# sheet3.net
KiCad netlist of a schematic drawn in Altium Designer
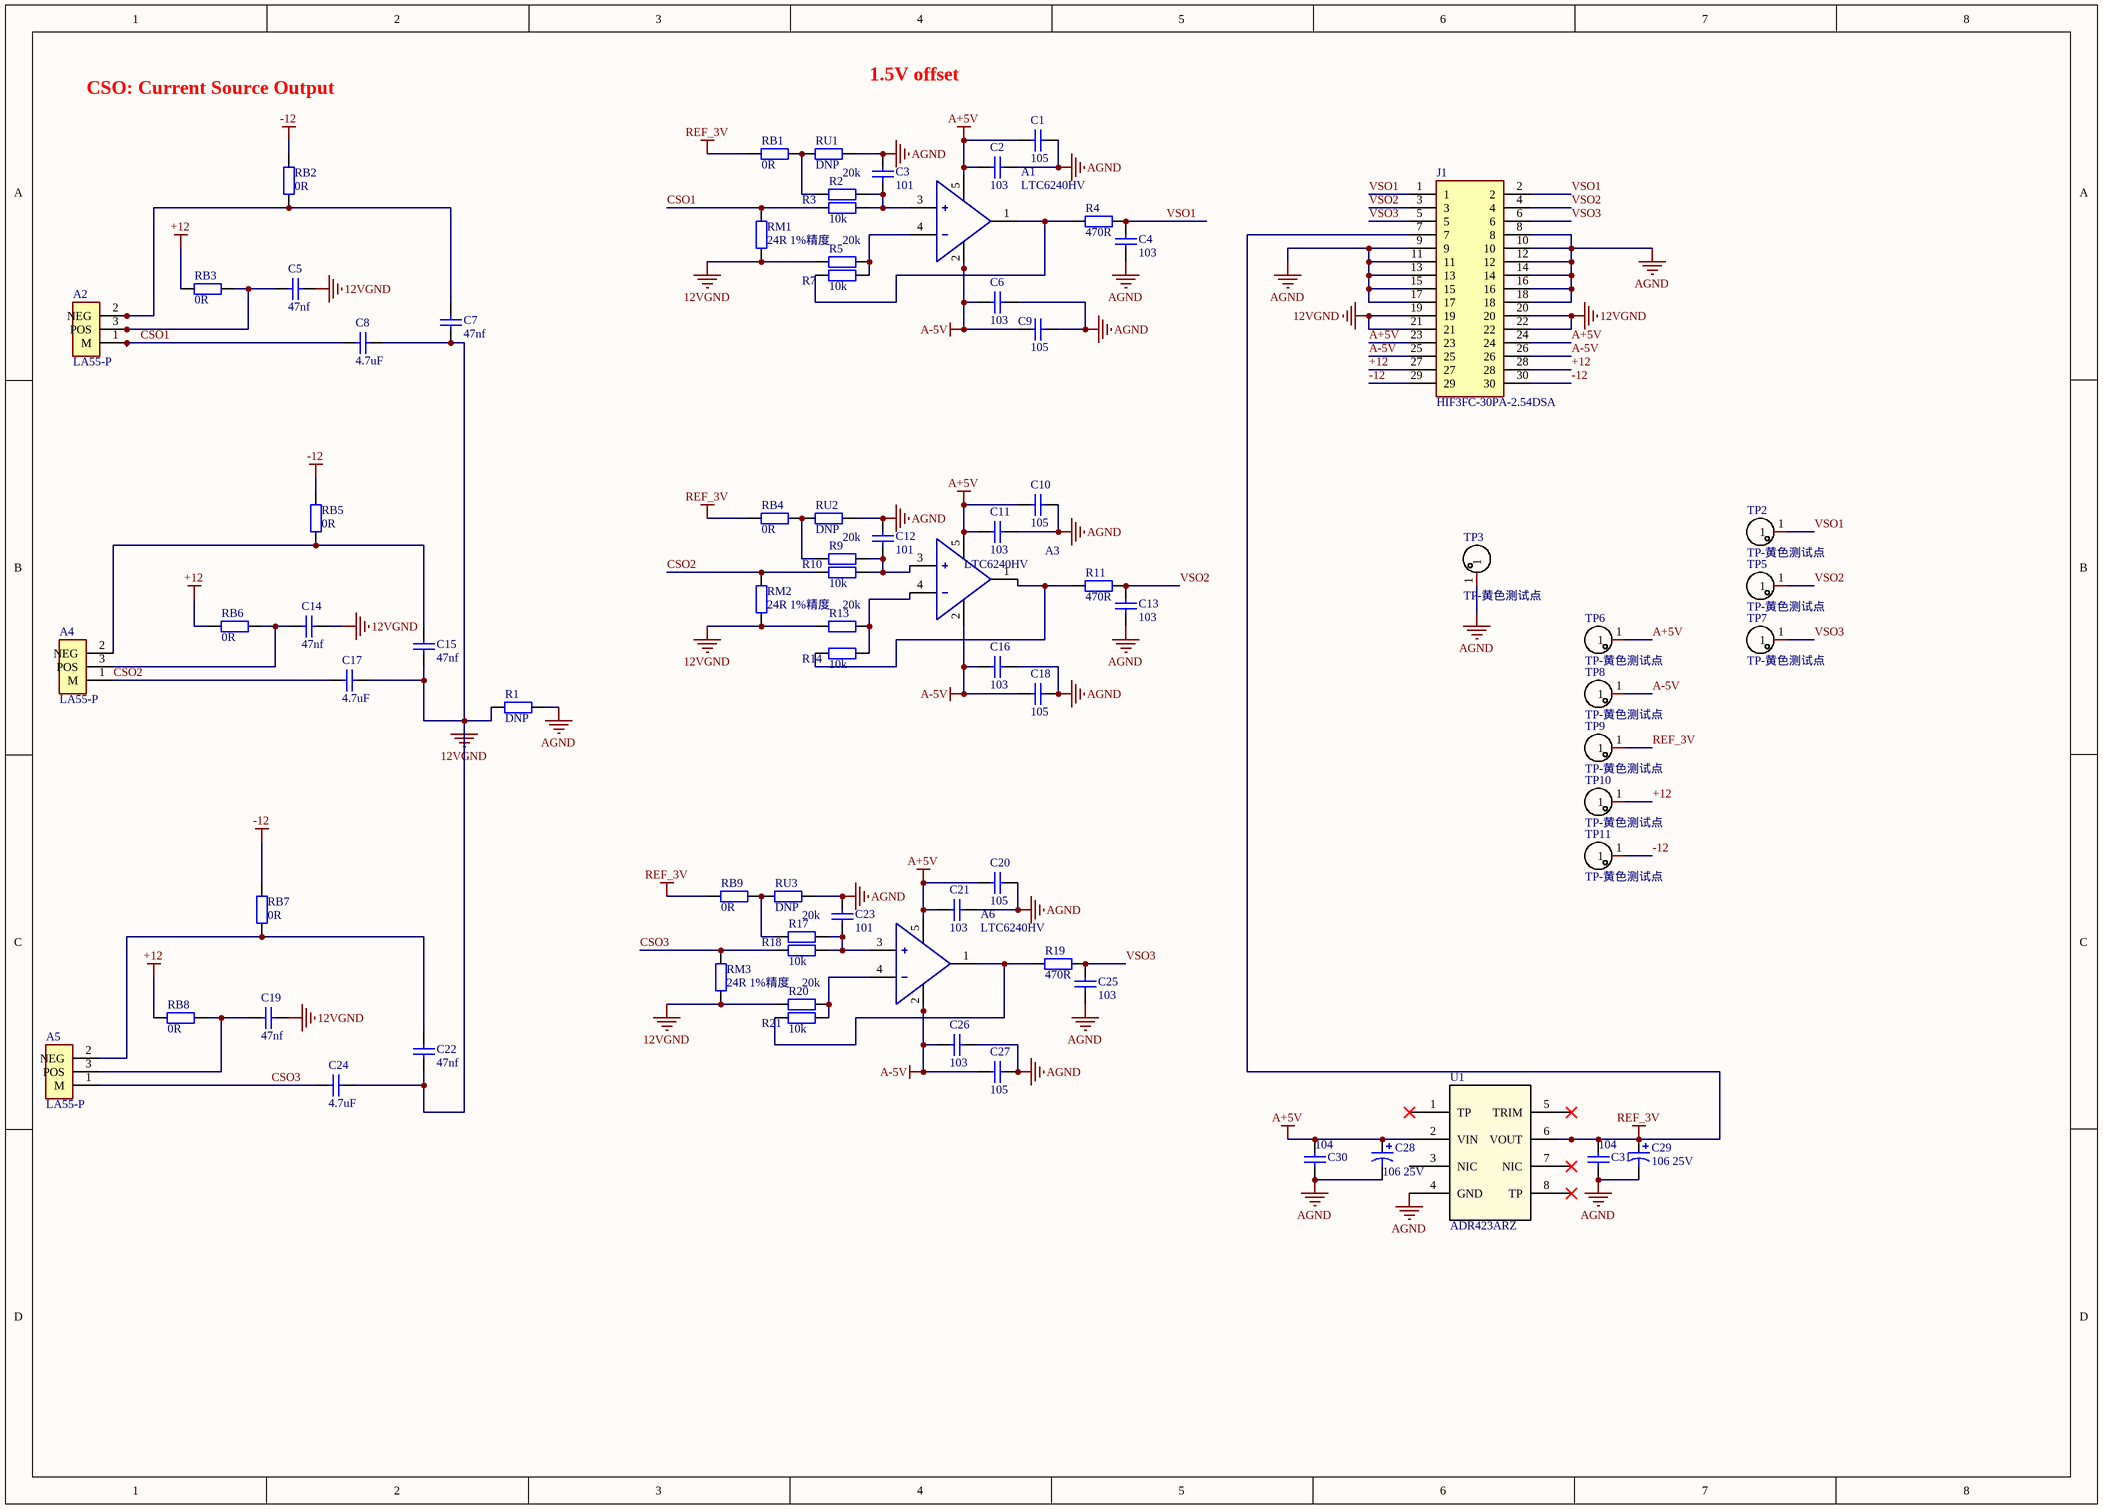
[diagram p0: sheet3.SchDoc]

(export (version "E")
  (design (tool "Eeschema 10.0.6"))
  (components
    (comp (ref "A1")
      (value "LTC6240HV")
      (footprint "SOT95P280X100-5N")
      (description "OP AMP, +-5.5V, 18MHZ, 10V/US, 5TSOT23")
      (libsource (lib "Project_Arsene") (part "AO_LTC6240HV"))
    )
    (comp (ref "A2")
      (value "LA55-P")
      (footprint "XDCR_LA55-P")
      (description "Current Sensor 50A 1 Channel Hall Effect, Closed Loop Bidirectional Module, Single Pass Through")
      (fields (field (name "MP") "LA 55-P") (field (name "MF") "LEM USA"))
      (libsource (lib "LA55-P") (part "LA55-P"))
    )
    (comp (ref "A3")
      (value "LTC6240HV")
      (footprint "SOT95P280X100-5N")
      (description "OP AMP, +-5.5V, 18MHZ, 10V/US, 5TSOT23")
      (libsource (lib "Project_Arsene") (part "AO_LTC6240HV"))
    )
    (comp (ref "A4")
      (value "LA55-P")
      (footprint "XDCR_LA55-P")
      (description "Current Sensor 50A 1 Channel Hall Effect, Closed Loop Bidirectional Module, Single Pass Through")
      (fields (field (name "MP") "LA 55-P") (field (name "MF") "LEM USA"))
      (libsource (lib "LA55-P") (part "LA55-P"))
    )
    (comp (ref "A5")
      (value "LA55-P")
      (footprint "XDCR_LA55-P")
      (description "Current Sensor 50A 1 Channel Hall Effect, Closed Loop Bidirectional Module, Single Pass Through")
      (fields (field (name "MP") "LA 55-P") (field (name "MF") "LEM USA"))
      (libsource (lib "LA55-P") (part "LA55-P"))
    )
    (comp (ref "A6")
      (value "LTC6240HV")
      (footprint "SOT95P280X100-5N")
      (description "OP AMP, +-5.5V, 18MHZ, 10V/US, 5TSOT23")
      (libsource (lib "Project_Arsene") (part "AO_LTC6240HV"))
    )
    (comp (ref "C1")
      (value "105")
      (footprint "0805")
      (description "Capacitor")
      (fields (field (name "PUBLISHER") "Altium Limited"))
      (libsource (lib "Miscellaneous Devices") (part "Cap"))
    )
    (comp (ref "C2")
      (value "103")
      (footprint "0805")
      (description "Capacitor")
      (fields (field (name "PUBLISHER") "Altium Limited"))
      (libsource (lib "Miscellaneous Devices") (part "Cap"))
    )
    (comp (ref "C3")
      (value "101")
      (footprint "0805")
      (description "Capacitor")
      (fields (field (name "PUBLISHER") "Altium Limited"))
      (libsource (lib "Miscellaneous Devices") (part "Cap"))
    )
    (comp (ref "C4")
      (value "103")
      (footprint "0805")
      (description "Capacitor")
      (fields (field (name "PUBLISHER") "Altium Limited"))
      (libsource (lib "Miscellaneous Devices") (part "Cap"))
    )
    (comp (ref "C5")
      (value "47nf")
      (footprint "0805")
      (description "Capacitor (Semiconductor SIM Model)")
      (fields (field (name "PUBLISHER") "Altium Limited"))
      (libsource (lib "Miscellaneous Devices") (part "Cap Semi"))
    )
    (comp (ref "C6")
      (value "103")
      (footprint "0805")
      (description "Capacitor")
      (fields (field (name "PUBLISHER") "Altium Limited"))
      (libsource (lib "Miscellaneous Devices") (part "Cap"))
    )
    (comp (ref "C7")
      (value "47nf")
      (footprint "0805")
      (description "Capacitor (Semiconductor SIM Model)")
      (fields (field (name "PUBLISHER") "Altium Limited"))
      (libsource (lib "Miscellaneous Devices") (part "Cap Semi"))
    )
    (comp (ref "C8")
      (value "4.7uF")
      (footprint "0805")
      (description "Capacitor (Semiconductor SIM Model)")
      (fields (field (name "PUBLISHER") "Altium Limited"))
      (libsource (lib "Miscellaneous Devices") (part "Cap Semi"))
    )
    (comp (ref "C9")
      (value "105")
      (footprint "0805")
      (description "Capacitor")
      (fields (field (name "PUBLISHER") "Altium Limited"))
      (libsource (lib "Miscellaneous Devices") (part "Cap"))
    )
    (comp (ref "C10")
      (value "105")
      (footprint "0805")
      (description "Capacitor")
      (fields (field (name "PUBLISHER") "Altium Limited"))
      (libsource (lib "Miscellaneous Devices") (part "Cap"))
    )
    (comp (ref "C11")
      (value "103")
      (footprint "0805")
      (description "Capacitor")
      (fields (field (name "PUBLISHER") "Altium Limited"))
      (libsource (lib "Miscellaneous Devices") (part "Cap"))
    )
    (comp (ref "C12")
      (value "101")
      (footprint "0805")
      (description "Capacitor")
      (fields (field (name "PUBLISHER") "Altium Limited"))
      (libsource (lib "Miscellaneous Devices") (part "Cap"))
    )
    (comp (ref "C13")
      (value "103")
      (footprint "0805")
      (description "Capacitor")
      (fields (field (name "PUBLISHER") "Altium Limited"))
      (libsource (lib "Miscellaneous Devices") (part "Cap"))
    )
    (comp (ref "C14")
      (value "47nf")
      (footprint "0805")
      (description "Capacitor (Semiconductor SIM Model)")
      (fields (field (name "PUBLISHER") "Altium Limited"))
      (libsource (lib "Miscellaneous Devices") (part "Cap Semi"))
    )
    (comp (ref "C15")
      (value "47nf")
      (footprint "0805")
      (description "Capacitor (Semiconductor SIM Model)")
      (fields (field (name "PUBLISHER") "Altium Limited"))
      (libsource (lib "Miscellaneous Devices") (part "Cap Semi"))
    )
    (comp (ref "C16")
      (value "103")
      (footprint "0805")
      (description "Capacitor")
      (fields (field (name "PUBLISHER") "Altium Limited"))
      (libsource (lib "Miscellaneous Devices") (part "Cap"))
    )
    (comp (ref "C17")
      (value "4.7uF")
      (footprint "0805")
      (description "Capacitor (Semiconductor SIM Model)")
      (fields (field (name "PUBLISHER") "Altium Limited"))
      (libsource (lib "Miscellaneous Devices") (part "Cap Semi"))
    )
    (comp (ref "C18")
      (value "105")
      (footprint "0805")
      (description "Capacitor")
      (fields (field (name "PUBLISHER") "Altium Limited"))
      (libsource (lib "Miscellaneous Devices") (part "Cap"))
    )
    (comp (ref "C19")
      (value "47nf")
      (footprint "0805")
      (description "Capacitor (Semiconductor SIM Model)")
      (fields (field (name "PUBLISHER") "Altium Limited"))
      (libsource (lib "Miscellaneous Devices") (part "Cap Semi"))
    )
    (comp (ref "C20")
      (value "105")
      (footprint "0805")
      (description "Capacitor")
      (fields (field (name "PUBLISHER") "Altium Limited"))
      (libsource (lib "Miscellaneous Devices") (part "Cap"))
    )
    (comp (ref "C21")
      (value "103")
      (footprint "0805")
      (description "Capacitor")
      (fields (field (name "PUBLISHER") "Altium Limited"))
      (libsource (lib "Miscellaneous Devices") (part "Cap"))
    )
    (comp (ref "C22")
      (value "47nf")
      (footprint "0805")
      (description "Capacitor (Semiconductor SIM Model)")
      (fields (field (name "PUBLISHER") "Altium Limited"))
      (libsource (lib "Miscellaneous Devices") (part "Cap Semi"))
    )
    (comp (ref "C23")
      (value "101")
      (footprint "0805")
      (description "Capacitor")
      (fields (field (name "PUBLISHER") "Altium Limited"))
      (libsource (lib "Miscellaneous Devices") (part "Cap"))
    )
    (comp (ref "C24")
      (value "4.7uF")
      (footprint "0805")
      (description "Capacitor (Semiconductor SIM Model)")
      (fields (field (name "PUBLISHER") "Altium Limited"))
      (libsource (lib "Miscellaneous Devices") (part "Cap Semi"))
    )
    (comp (ref "C25")
      (value "103")
      (footprint "0805")
      (description "Capacitor")
      (fields (field (name "PUBLISHER") "Altium Limited"))
      (libsource (lib "Miscellaneous Devices") (part "Cap"))
    )
    (comp (ref "C26")
      (value "103")
      (footprint "0805")
      (description "Capacitor")
      (fields (field (name "PUBLISHER") "Altium Limited"))
      (libsource (lib "Miscellaneous Devices") (part "Cap"))
    )
    (comp (ref "C27")
      (value "105")
      (footprint "0805")
      (description "Capacitor")
      (fields (field (name "PUBLISHER") "Altium Limited"))
      (libsource (lib "Miscellaneous Devices") (part "Cap"))
    )
    (comp (ref "C28")
      (value "106 25V")
      (footprint "1206 (钽电容)")
      (description "Polarized Capacitor (Surface Mount)")
      (fields (field (name "PUBLISHER") "Altium Limited"))
      (libsource (lib "Miscellaneous Devices") (part "Cap Pol3"))
    )
    (comp (ref "C29")
      (value "106 25V")
      (footprint "1206 (钽电容)")
      (description "Polarized Capacitor (Surface Mount)")
      (fields (field (name "PUBLISHER") "Altium Limited"))
      (libsource (lib "Miscellaneous Devices") (part "Cap Pol3"))
    )
    (comp (ref "C30")
      (value "104")
      (footprint "0805")
      (description "Capacitor (Semiconductor SIM Model)")
      (fields (field (name "PUBLISHER") "Altium Limited"))
      (libsource (lib "Miscellaneous Devices") (part "Cap Semi"))
    )
    (comp (ref "C31")
      (value "104")
      (footprint "0805")
      (description "Capacitor (Semiconductor SIM Model)")
      (fields (field (name "PUBLISHER") "Altium Limited"))
      (libsource (lib "Miscellaneous Devices") (part "Cap Semi"))
    )
    (comp (ref "J1")
      (value "HIF3FC-30PA-2.54DSA")
      (footprint "Project_Oshinoko:SHDR30W50P254_2X15_4560X850X1200P")
      (description "Connector")
      (fields
        (field (name "MANUFACTURER_PART_NUMBER") "HIF3FC-30PA-2.54DSA(71)")
        (field (name "MOUSER PART NUMBER") "798-HIF3FC30PA254D71")
      )
      (libsource (lib "Project_Arsene") (part "HIF3FC-30PA-2.54DSA"))
    )
    (comp (ref "R1")
      (value "DNP")
      (footprint "0805")
      (description "Resistor")
      (fields (field (name "PUBLISHER") "Altium Limited"))
      (libsource (lib "") (part "Res2_1"))
    )
    (comp (ref "R2")
      (value "20k")
      (footprint "0805")
      (description "Resistor")
      (fields (field (name "PUBLISHER") "Altium Limited"))
      (libsource (lib "") (part "Res2_2"))
    )
    (comp (ref "R3")
      (value "10k")
      (footprint "0805")
      (description "Resistor")
      (fields (field (name "PUBLISHER") "Altium Limited"))
      (libsource (lib "") (part "Res2_2"))
    )
    (comp (ref "R4")
      (value "470R")
      (footprint "0805")
      (description "Resistor")
      (fields (field (name "PUBLISHER") "Altium Limited"))
      (libsource (lib "") (part "Res2_1"))
    )
    (comp (ref "R5")
      (value "20k")
      (footprint "0805")
      (description "Resistor")
      (fields (field (name "PUBLISHER") "Altium Limited"))
      (libsource (lib "") (part "Res2_2"))
    )
    (comp (ref "R7")
      (value "10k")
      (footprint "0805")
      (description "Resistor")
      (fields (field (name "PUBLISHER") "Altium Limited"))
      (libsource (lib "") (part "Res2_2"))
    )
    (comp (ref "R9")
      (value "20k")
      (footprint "0805")
      (description "Resistor")
      (fields (field (name "PUBLISHER") "Altium Limited"))
      (libsource (lib "") (part "Res2_2"))
    )
    (comp (ref "R10")
      (value "10k")
      (footprint "0805")
      (description "Resistor")
      (fields (field (name "PUBLISHER") "Altium Limited"))
      (libsource (lib "") (part "Res2_2"))
    )
    (comp (ref "R11")
      (value "470R")
      (footprint "0805")
      (description "Resistor")
      (fields (field (name "PUBLISHER") "Altium Limited"))
      (libsource (lib "") (part "Res2_1"))
    )
    (comp (ref "R13")
      (value "20k")
      (footprint "0805")
      (description "Resistor")
      (fields (field (name "PUBLISHER") "Altium Limited"))
      (libsource (lib "") (part "Res2_2"))
    )
    (comp (ref "R14")
      (value "10k")
      (footprint "0805")
      (description "Resistor")
      (fields (field (name "PUBLISHER") "Altium Limited"))
      (libsource (lib "") (part "Res2_2"))
    )
    (comp (ref "R17")
      (value "20k")
      (footprint "0805")
      (description "Resistor")
      (fields (field (name "PUBLISHER") "Altium Limited"))
      (libsource (lib "") (part "Res2_2"))
    )
    (comp (ref "R18")
      (value "10k")
      (footprint "0805")
      (description "Resistor")
      (fields (field (name "PUBLISHER") "Altium Limited"))
      (libsource (lib "") (part "Res2_2"))
    )
    (comp (ref "R19")
      (value "470R")
      (footprint "0805")
      (description "Resistor")
      (fields (field (name "PUBLISHER") "Altium Limited"))
      (libsource (lib "") (part "Res2_1"))
    )
    (comp (ref "R20")
      (value "20k")
      (footprint "0805")
      (description "Resistor")
      (fields (field (name "PUBLISHER") "Altium Limited"))
      (libsource (lib "") (part "Res2_2"))
    )
    (comp (ref "R21")
      (value "10k")
      (footprint "0805")
      (description "Resistor")
      (fields (field (name "PUBLISHER") "Altium Limited"))
      (libsource (lib "") (part "Res2_2"))
    )
    (comp (ref "RB1")
      (value "0R")
      (footprint "0805")
      (description "Resistor")
      (fields (field (name "PUBLISHER") "Altium Limited"))
      (libsource (lib "") (part "Res2_2"))
    )
    (comp (ref "RB2")
      (value "0R")
      (footprint "0805")
      (description "Resistor")
      (fields (field (name "PUBLISHER") "Altium Limited"))
      (libsource (lib "Miscellaneous Devices") (part "Res2"))
    )
    (comp (ref "RB3")
      (value "0R")
      (footprint "0805")
      (description "Resistor")
      (fields (field (name "PUBLISHER") "Altium Limited"))
      (libsource (lib "") (part "Res2_2"))
    )
    (comp (ref "RB4")
      (value "0R")
      (footprint "0805")
      (description "Resistor")
      (fields (field (name "PUBLISHER") "Altium Limited"))
      (libsource (lib "") (part "Res2_2"))
    )
    (comp (ref "RB5")
      (value "0R")
      (footprint "0805")
      (description "Resistor")
      (fields (field (name "PUBLISHER") "Altium Limited"))
      (libsource (lib "Miscellaneous Devices") (part "Res2"))
    )
    (comp (ref "RB6")
      (value "0R")
      (footprint "0805")
      (description "Resistor")
      (fields (field (name "PUBLISHER") "Altium Limited"))
      (libsource (lib "") (part "Res2_2"))
    )
    (comp (ref "RB7")
      (value "0R")
      (footprint "0805")
      (description "Resistor")
      (fields (field (name "PUBLISHER") "Altium Limited"))
      (libsource (lib "Miscellaneous Devices") (part "Res2"))
    )
    (comp (ref "RB8")
      (value "0R")
      (footprint "0805")
      (description "Resistor")
      (fields (field (name "PUBLISHER") "Altium Limited"))
      (libsource (lib "") (part "Res2_2"))
    )
    (comp (ref "RB9")
      (value "0R")
      (footprint "0805")
      (description "Resistor")
      (fields (field (name "PUBLISHER") "Altium Limited"))
      (libsource (lib "") (part "Res2_2"))
    )
    (comp (ref "RM1")
      (value "24R 1%精度")
      (footprint "2512")
      (description "Resistor")
      (fields (field (name "PUBLISHER") "Altium Limited"))
      (libsource (lib "") (part "Res2_3"))
    )
    (comp (ref "RM2")
      (value "24R 1%精度")
      (footprint "2512")
      (description "Resistor")
      (fields (field (name "PUBLISHER") "Altium Limited"))
      (libsource (lib "") (part "Res2_3"))
    )
    (comp (ref "RM3")
      (value "24R 1%精度")
      (footprint "2512")
      (description "Resistor")
      (fields (field (name "PUBLISHER") "Altium Limited"))
      (libsource (lib "") (part "Res2_3"))
    )
    (comp (ref "RU1")
      (value "DNP")
      (footprint "0805")
      (description "Resistor")
      (fields (field (name "PUBLISHER") "Altium Limited"))
      (libsource (lib "") (part "Res2_2"))
    )
    (comp (ref "RU2")
      (value "DNP")
      (footprint "0805")
      (description "Resistor")
      (fields (field (name "PUBLISHER") "Altium Limited"))
      (libsource (lib "") (part "Res2_2"))
    )
    (comp (ref "RU3")
      (value "DNP")
      (footprint "0805")
      (description "Resistor")
      (fields (field (name "PUBLISHER") "Altium Limited"))
      (libsource (lib "") (part "Res2_2"))
    )
    (comp (ref "TP2")
      (value "TP-黄色测试点")
      (footprint "TESTPOINT-TH_BD1.0")
      (fields (field (name "NAME") "TP-黄色测试点"))
      (libsource (lib "Project_Oshinoko") (part "TP-黄色测试点"))
    )
    (comp (ref "TP3")
      (value "TP-黄色测试点")
      (footprint "TESTPOINT-TH_BD1.0")
      (fields (field (name "NAME") "TP-黄色测试点"))
      (libsource (lib "Project_Oshinoko") (part "TP-黄色测试点"))
    )
    (comp (ref "TP5")
      (value "TP-黄色测试点")
      (footprint "TESTPOINT-TH_BD1.0")
      (fields (field (name "NAME") "TP-黄色测试点"))
      (libsource (lib "Project_Oshinoko") (part "TP-黄色测试点"))
    )
    (comp (ref "TP6")
      (value "TP-黄色测试点")
      (footprint "TESTPOINT-TH_BD1.0")
      (fields (field (name "NAME") "TP-黄色测试点"))
      (libsource (lib "Project_Oshinoko") (part "TP-黄色测试点"))
    )
    (comp (ref "TP7")
      (value "TP-黄色测试点")
      (footprint "TESTPOINT-TH_BD1.0")
      (fields (field (name "NAME") "TP-黄色测试点"))
      (libsource (lib "Project_Oshinoko") (part "TP-黄色测试点"))
    )
    (comp (ref "TP8")
      (value "TP-黄色测试点")
      (footprint "TESTPOINT-TH_BD1.0")
      (fields (field (name "NAME") "TP-黄色测试点"))
      (libsource (lib "Project_Oshinoko") (part "TP-黄色测试点"))
    )
    (comp (ref "TP9")
      (value "TP-黄色测试点")
      (footprint "TESTPOINT-TH_BD1.0")
      (fields (field (name "NAME") "TP-黄色测试点"))
      (libsource (lib "Project_Oshinoko") (part "TP-黄色测试点"))
    )
    (comp (ref "TP10")
      (value "TP-黄色测试点")
      (footprint "TESTPOINT-TH_BD1.0")
      (fields (field (name "NAME") "TP-黄色测试点"))
      (libsource (lib "Project_Oshinoko") (part "TP-黄色测试点"))
    )
    (comp (ref "TP11")
      (value "TP-黄色测试点")
      (footprint "TESTPOINT-TH_BD1.0")
      (fields (field (name "NAME") "TP-黄色测试点"))
      (libsource (lib "Project_Oshinoko") (part "TP-黄色测试点"))
    )
    (comp (ref "U1")
      (value "ADR423ARZ")
      (footprint "SOIC-8")
      (description "Imported")
      (libsource (lib "adr423") (part "ADR423ARZ"))
    )
  )
  (nets
    (net (code "1") (name "+12") (class "Default")
      (node (ref "J1") (pin "27") (pinfunction "27_27") (pintype "passive"))
      (node (ref "J1") (pin "28") (pinfunction "28_28") (pintype "passive"))
      (node (ref "RB3") (pin "1") (pinfunction "1_1") (pintype "passive"))
      (node (ref "RB6") (pin "1") (pinfunction "1_1") (pintype "passive"))
      (node (ref "RB8") (pin "1") (pinfunction "1_1") (pintype "passive"))
      (node (ref "TP10") (pin "1") (pinfunction "1_1") (pintype "passive"))
    )
    (net (code "2") (name "-12") (class "Default")
      (node (ref "J1") (pin "29") (pinfunction "29_29") (pintype "passive"))
      (node (ref "J1") (pin "30") (pinfunction "30_30") (pintype "passive"))
      (node (ref "RB2") (pin "2") (pinfunction "2_2") (pintype "passive"))
      (node (ref "RB5") (pin "2") (pinfunction "2_2") (pintype "passive"))
      (node (ref "RB7") (pin "2") (pinfunction "2_2") (pintype "passive"))
      (node (ref "TP11") (pin "1") (pinfunction "1_1") (pintype "passive"))
    )
    (net (code "3") (name "/CSO1") (class "Default")
      (node (ref "A2") (pin "1") (pinfunction "M_1") (pintype "power_in"))
      (node (ref "C8") (pin "1") (pinfunction "1_1") (pintype "passive"))
      (node (ref "R3") (pin "1") (pinfunction "1_1") (pintype "passive"))
      (node (ref "RM1") (pin "1") (pinfunction "1_1") (pintype "passive"))
    )
    (net (code "4") (name "/CSO2") (class "Default")
      (node (ref "A4") (pin "1") (pinfunction "M_1") (pintype "power_in"))
      (node (ref "C17") (pin "1") (pinfunction "1_1") (pintype "passive"))
      (node (ref "R10") (pin "1") (pinfunction "1_1") (pintype "passive"))
      (node (ref "RM2") (pin "1") (pinfunction "1_1") (pintype "passive"))
    )
    (net (code "5") (name "/CSO3") (class "Default")
      (node (ref "A5") (pin "1") (pinfunction "M_1") (pintype "power_in"))
      (node (ref "C24") (pin "1") (pinfunction "1_1") (pintype "passive"))
      (node (ref "R18") (pin "1") (pinfunction "1_1") (pintype "passive"))
      (node (ref "RM3") (pin "1") (pinfunction "1_1") (pintype "passive"))
    )
    (net (code "6") (name "/VSO1") (class "Default")
      (node (ref "C4") (pin "2") (pinfunction "2_2") (pintype "passive"))
      (node (ref "J1") (pin "1") (pinfunction "1_1") (pintype "passive"))
      (node (ref "J1") (pin "2") (pinfunction "2_2") (pintype "passive"))
      (node (ref "R4") (pin "1") (pinfunction "1_1") (pintype "passive"))
      (node (ref "TP2") (pin "1") (pinfunction "1_1") (pintype "passive"))
    )
    (net (code "7") (name "/VSO2") (class "Default")
      (node (ref "C13") (pin "2") (pinfunction "2_2") (pintype "passive"))
      (node (ref "J1") (pin "3") (pinfunction "3_3") (pintype "passive"))
      (node (ref "J1") (pin "4") (pinfunction "4_4") (pintype "passive"))
      (node (ref "R11") (pin "1") (pinfunction "1_1") (pintype "passive"))
      (node (ref "TP5") (pin "1") (pinfunction "1_1") (pintype "passive"))
    )
    (net (code "8") (name "/VSO3") (class "Default")
      (node (ref "C25") (pin "2") (pinfunction "2_2") (pintype "passive"))
      (node (ref "J1") (pin "5") (pinfunction "5_5") (pintype "passive"))
      (node (ref "J1") (pin "6") (pinfunction "6_6") (pintype "passive"))
      (node (ref "R19") (pin "1") (pinfunction "1_1") (pintype "passive"))
      (node (ref "TP7") (pin "1") (pinfunction "1_1") (pintype "passive"))
    )
    (net (code "9") (name "12VGND") (class "Default")
      (node (ref "C14") (pin "1") (pinfunction "1_1") (pintype "passive"))
      (node (ref "C15") (pin "2") (pinfunction "2_2") (pintype "passive"))
      (node (ref "C17") (pin "2") (pinfunction "2_2") (pintype "passive"))
      (node (ref "C19") (pin "1") (pinfunction "1_1") (pintype "passive"))
      (node (ref "C22") (pin "2") (pinfunction "2_2") (pintype "passive"))
      (node (ref "C24") (pin "2") (pinfunction "2_2") (pintype "passive"))
      (node (ref "C5") (pin "1") (pinfunction "1_1") (pintype "passive"))
      (node (ref "C7") (pin "2") (pinfunction "2_2") (pintype "passive"))
      (node (ref "C8") (pin "2") (pinfunction "2_2") (pintype "passive"))
      (node (ref "J1") (pin "19") (pinfunction "19_19") (pintype "passive"))
      (node (ref "J1") (pin "20") (pinfunction "20_20") (pintype "passive"))
      (node (ref "J1") (pin "21") (pinfunction "21_21") (pintype "passive"))
      (node (ref "J1") (pin "22") (pinfunction "22_22") (pintype "passive"))
      (node (ref "R1") (pin "2") (pinfunction "2_2") (pintype "passive"))
      (node (ref "R13") (pin "1") (pinfunction "1_1") (pintype "passive"))
      (node (ref "R20") (pin "1") (pinfunction "1_1") (pintype "passive"))
      (node (ref "R5") (pin "1") (pinfunction "1_1") (pintype "passive"))
      (node (ref "RM1") (pin "2") (pinfunction "2_2") (pintype "passive"))
      (node (ref "RM2") (pin "2") (pinfunction "2_2") (pintype "passive"))
      (node (ref "RM3") (pin "2") (pinfunction "2_2") (pintype "passive"))
    )
    (net (code "10") (name "A+5V") (class "Default")
      (node (ref "A1") (pin "5") (pinfunction "Vcc_5") (pintype "passive"))
      (node (ref "A3") (pin "5") (pinfunction "Vcc_5") (pintype "passive"))
      (node (ref "A6") (pin "5") (pinfunction "Vcc_5") (pintype "passive"))
      (node (ref "C1") (pin "2") (pinfunction "2_2") (pintype "passive"))
      (node (ref "C10") (pin "2") (pinfunction "2_2") (pintype "passive"))
      (node (ref "C11") (pin "2") (pinfunction "2_2") (pintype "passive"))
      (node (ref "C2") (pin "2") (pinfunction "2_2") (pintype "passive"))
      (node (ref "C20") (pin "2") (pinfunction "2_2") (pintype "passive"))
      (node (ref "C21") (pin "2") (pinfunction "2_2") (pintype "passive"))
      (node (ref "C28") (pin "1") (pinfunction "1_1") (pintype "passive"))
      (node (ref "C30") (pin "2") (pinfunction "2_2") (pintype "passive"))
      (node (ref "J1") (pin "23") (pinfunction "23_23") (pintype "passive"))
      (node (ref "J1") (pin "24") (pinfunction "24_24") (pintype "passive"))
      (node (ref "TP6") (pin "1") (pinfunction "1_1") (pintype "passive"))
      (node (ref "U1") (pin "2") (pinfunction "VIN_2") (pintype "passive"))
    )
    (net (code "11") (name "A-5V") (class "Default")
      (node (ref "A1") (pin "2") (pinfunction "Vee_2") (pintype "passive"))
      (node (ref "A3") (pin "2") (pinfunction "Vee_2") (pintype "passive"))
      (node (ref "A6") (pin "2") (pinfunction "Vee_2") (pintype "passive"))
      (node (ref "C16") (pin "2") (pinfunction "2_2") (pintype "passive"))
      (node (ref "C18") (pin "2") (pinfunction "2_2") (pintype "passive"))
      (node (ref "C26") (pin "2") (pinfunction "2_2") (pintype "passive"))
      (node (ref "C27") (pin "2") (pinfunction "2_2") (pintype "passive"))
      (node (ref "C6") (pin "2") (pinfunction "2_2") (pintype "passive"))
      (node (ref "C9") (pin "2") (pinfunction "2_2") (pintype "passive"))
      (node (ref "J1") (pin "25") (pinfunction "25_25") (pintype "passive"))
      (node (ref "J1") (pin "26") (pinfunction "26_26") (pintype "passive"))
      (node (ref "TP8") (pin "1") (pinfunction "1_1") (pintype "passive"))
    )
    (net (code "12") (name "AGND") (class "Default")
      (node (ref "C1") (pin "1") (pinfunction "1_1") (pintype "passive"))
      (node (ref "C10") (pin "1") (pinfunction "1_1") (pintype "passive"))
      (node (ref "C11") (pin "1") (pinfunction "1_1") (pintype "passive"))
      (node (ref "C12") (pin "2") (pinfunction "2_2") (pintype "passive"))
      (node (ref "C13") (pin "1") (pinfunction "1_1") (pintype "passive"))
      (node (ref "C16") (pin "1") (pinfunction "1_1") (pintype "passive"))
      (node (ref "C18") (pin "1") (pinfunction "1_1") (pintype "passive"))
      (node (ref "C2") (pin "1") (pinfunction "1_1") (pintype "passive"))
      (node (ref "C20") (pin "1") (pinfunction "1_1") (pintype "passive"))
      (node (ref "C21") (pin "1") (pinfunction "1_1") (pintype "passive"))
      (node (ref "C23") (pin "2") (pinfunction "2_2") (pintype "passive"))
      (node (ref "C25") (pin "1") (pinfunction "1_1") (pintype "passive"))
      (node (ref "C26") (pin "1") (pinfunction "1_1") (pintype "passive"))
      (node (ref "C27") (pin "1") (pinfunction "1_1") (pintype "passive"))
      (node (ref "C28") (pin "2") (pinfunction "2_2") (pintype "passive"))
      (node (ref "C29") (pin "2") (pinfunction "2_2") (pintype "passive"))
      (node (ref "C3") (pin "2") (pinfunction "2_2") (pintype "passive"))
      (node (ref "C30") (pin "1") (pinfunction "1_1") (pintype "passive"))
      (node (ref "C31") (pin "1") (pinfunction "1_1") (pintype "passive"))
      (node (ref "C4") (pin "1") (pinfunction "1_1") (pintype "passive"))
      (node (ref "C6") (pin "1") (pinfunction "1_1") (pintype "passive"))
      (node (ref "C9") (pin "1") (pinfunction "1_1") (pintype "passive"))
      (node (ref "J1") (pin "10") (pinfunction "10_10") (pintype "passive"))
      (node (ref "J1") (pin "11") (pinfunction "11_11") (pintype "passive"))
      (node (ref "J1") (pin "12") (pinfunction "12_12") (pintype "passive"))
      (node (ref "J1") (pin "13") (pinfunction "13_13") (pintype "passive"))
      (node (ref "J1") (pin "14") (pinfunction "14_14") (pintype "passive"))
      (node (ref "J1") (pin "15") (pinfunction "15_15") (pintype "passive"))
      (node (ref "J1") (pin "16") (pinfunction "16_16") (pintype "passive"))
      (node (ref "J1") (pin "17") (pinfunction "17_17") (pintype "passive"))
      (node (ref "J1") (pin "18") (pinfunction "18_18") (pintype "passive"))
      (node (ref "J1") (pin "8") (pinfunction "8_8") (pintype "passive"))
      (node (ref "J1") (pin "9") (pinfunction "9_9") (pintype "passive"))
      (node (ref "R1") (pin "1") (pinfunction "1_1") (pintype "passive"))
      (node (ref "RU1") (pin "2") (pinfunction "2_2") (pintype "passive"))
      (node (ref "RU2") (pin "2") (pinfunction "2_2") (pintype "passive"))
      (node (ref "RU3") (pin "2") (pinfunction "2_2") (pintype "passive"))
      (node (ref "TP3") (pin "1") (pinfunction "1_1") (pintype "passive"))
      (node (ref "U1") (pin "4") (pinfunction "GND_4") (pintype "passive"))
    )
    (net (code "13") (name "Net-(A1-+IN)") (class "Default")
      (node (ref "A1") (pin "3") (pinfunction "+IN_3") (pintype "passive"))
      (node (ref "C3") (pin "1") (pinfunction "1_1") (pintype "passive"))
      (node (ref "R2") (pin "2") (pinfunction "2_2") (pintype "passive"))
      (node (ref "R3") (pin "2") (pinfunction "2_2") (pintype "passive"))
    )
    (net (code "14") (name "Net-(A1--IN)") (class "Default")
      (node (ref "A1") (pin "4") (pinfunction "-IN_4") (pintype "passive"))
      (node (ref "R5") (pin "2") (pinfunction "2_2") (pintype "passive"))
      (node (ref "R7") (pin "2") (pinfunction "2_2") (pintype "passive"))
    )
    (net (code "15") (name "Net-(A1-out)") (class "Default")
      (node (ref "A1") (pin "1") (pinfunction "out_1") (pintype "passive"))
      (node (ref "R4") (pin "2") (pinfunction "2_2") (pintype "passive"))
      (node (ref "R7") (pin "1") (pinfunction "1_1") (pintype "passive"))
    )
    (net (code "16") (name "Net-(A2-NEG)") (class "Default")
      (node (ref "A2") (pin "2") (pinfunction "NEG_2") (pintype "power_in"))
      (node (ref "C7") (pin "1") (pinfunction "1_1") (pintype "passive"))
      (node (ref "RB2") (pin "1") (pinfunction "1_1") (pintype "passive"))
    )
    (net (code "17") (name "Net-(A2-POS)") (class "Default")
      (node (ref "A2") (pin "3") (pinfunction "POS_3") (pintype "power_in"))
      (node (ref "C5") (pin "2") (pinfunction "2_2") (pintype "passive"))
      (node (ref "RB3") (pin "2") (pinfunction "2_2") (pintype "passive"))
    )
    (net (code "18") (name "Net-(A3-+IN)") (class "Default")
      (node (ref "A3") (pin "3") (pinfunction "+IN_3") (pintype "passive"))
      (node (ref "C12") (pin "1") (pinfunction "1_1") (pintype "passive"))
      (node (ref "R10") (pin "2") (pinfunction "2_2") (pintype "passive"))
      (node (ref "R9") (pin "2") (pinfunction "2_2") (pintype "passive"))
    )
    (net (code "19") (name "Net-(A3--IN)") (class "Default")
      (node (ref "A3") (pin "4") (pinfunction "-IN_4") (pintype "passive"))
      (node (ref "R13") (pin "2") (pinfunction "2_2") (pintype "passive"))
      (node (ref "R14") (pin "2") (pinfunction "2_2") (pintype "passive"))
    )
    (net (code "20") (name "Net-(A3-out)") (class "Default")
      (node (ref "A3") (pin "1") (pinfunction "out_1") (pintype "passive"))
      (node (ref "R11") (pin "2") (pinfunction "2_2") (pintype "passive"))
      (node (ref "R14") (pin "1") (pinfunction "1_1") (pintype "passive"))
    )
    (net (code "21") (name "Net-(A4-NEG)") (class "Default")
      (node (ref "A4") (pin "2") (pinfunction "NEG_2") (pintype "power_in"))
      (node (ref "C15") (pin "1") (pinfunction "1_1") (pintype "passive"))
      (node (ref "RB5") (pin "1") (pinfunction "1_1") (pintype "passive"))
    )
    (net (code "22") (name "Net-(A4-POS)") (class "Default")
      (node (ref "A4") (pin "3") (pinfunction "POS_3") (pintype "power_in"))
      (node (ref "C14") (pin "2") (pinfunction "2_2") (pintype "passive"))
      (node (ref "RB6") (pin "2") (pinfunction "2_2") (pintype "passive"))
    )
    (net (code "23") (name "Net-(A5-NEG)") (class "Default")
      (node (ref "A5") (pin "2") (pinfunction "NEG_2") (pintype "power_in"))
      (node (ref "C22") (pin "1") (pinfunction "1_1") (pintype "passive"))
      (node (ref "RB7") (pin "1") (pinfunction "1_1") (pintype "passive"))
    )
    (net (code "24") (name "Net-(A5-POS)") (class "Default")
      (node (ref "A5") (pin "3") (pinfunction "POS_3") (pintype "power_in"))
      (node (ref "C19") (pin "2") (pinfunction "2_2") (pintype "passive"))
      (node (ref "RB8") (pin "2") (pinfunction "2_2") (pintype "passive"))
    )
    (net (code "25") (name "Net-(A6-+IN)") (class "Default")
      (node (ref "A6") (pin "3") (pinfunction "+IN_3") (pintype "passive"))
      (node (ref "C23") (pin "1") (pinfunction "1_1") (pintype "passive"))
      (node (ref "R17") (pin "2") (pinfunction "2_2") (pintype "passive"))
      (node (ref "R18") (pin "2") (pinfunction "2_2") (pintype "passive"))
    )
    (net (code "26") (name "Net-(A6--IN)") (class "Default")
      (node (ref "A6") (pin "4") (pinfunction "-IN_4") (pintype "passive"))
      (node (ref "R20") (pin "2") (pinfunction "2_2") (pintype "passive"))
      (node (ref "R21") (pin "2") (pinfunction "2_2") (pintype "passive"))
    )
    (net (code "27") (name "Net-(A6-out)") (class "Default")
      (node (ref "A6") (pin "1") (pinfunction "out_1") (pintype "passive"))
      (node (ref "R19") (pin "2") (pinfunction "2_2") (pintype "passive"))
      (node (ref "R21") (pin "1") (pinfunction "1_1") (pintype "passive"))
    )
    (net (code "28") (name "Net-(R2-Pad1)") (class "Default")
      (node (ref "R2") (pin "1") (pinfunction "1_1") (pintype "passive"))
      (node (ref "RB1") (pin "2") (pinfunction "2_2") (pintype "passive"))
      (node (ref "RU1") (pin "1") (pinfunction "1_1") (pintype "passive"))
    )
    (net (code "29") (name "Net-(R9-Pad1)") (class "Default")
      (node (ref "R9") (pin "1") (pinfunction "1_1") (pintype "passive"))
      (node (ref "RB4") (pin "2") (pinfunction "2_2") (pintype "passive"))
      (node (ref "RU2") (pin "1") (pinfunction "1_1") (pintype "passive"))
    )
    (net (code "30") (name "Net-(R17-Pad1)") (class "Default")
      (node (ref "R17") (pin "1") (pinfunction "1_1") (pintype "passive"))
      (node (ref "RB9") (pin "2") (pinfunction "2_2") (pintype "passive"))
      (node (ref "RU3") (pin "1") (pinfunction "1_1") (pintype "passive"))
    )
    (net (code "31") (name "REF_3V") (class "Default")
      (node (ref "C29") (pin "1") (pinfunction "1_1") (pintype "passive"))
      (node (ref "C31") (pin "2") (pinfunction "2_2") (pintype "passive"))
      (node (ref "J1") (pin "7") (pinfunction "7_7") (pintype "passive"))
      (node (ref "RB1") (pin "1") (pinfunction "1_1") (pintype "passive"))
      (node (ref "RB4") (pin "1") (pinfunction "1_1") (pintype "passive"))
      (node (ref "RB9") (pin "1") (pinfunction "1_1") (pintype "passive"))
      (node (ref "TP9") (pin "1") (pinfunction "1_1") (pintype "passive"))
      (node (ref "U1") (pin "6") (pinfunction "VOUT_6") (pintype "passive"))
    )
    (net (code "32") (name "unconnected-(U1-NIC-Pad3)") (class "Default")
      (node (ref "U1") (pin "3") (pinfunction "NIC_3") (pintype "passive"))
    )
    (net (code "33") (name "unconnected-(U1-NIC-Pad7)") (class "Default")
      (node (ref "U1") (pin "7") (pinfunction "NIC_7") (pintype "passive+no_connect"))
    )
    (net (code "34") (name "unconnected-(U1-TP-Pad1)") (class "Default")
      (node (ref "U1") (pin "1") (pinfunction "TP_1") (pintype "passive+no_connect"))
    )
    (net (code "35") (name "unconnected-(U1-TP-Pad8)") (class "Default")
      (node (ref "U1") (pin "8") (pinfunction "TP_8") (pintype "passive+no_connect"))
    )
    (net (code "36") (name "unconnected-(U1-TRIM-Pad5)") (class "Default")
      (node (ref "U1") (pin "5") (pinfunction "TRIM_5") (pintype "passive+no_connect"))
    )
  )
)
